# Rotary.net
KiCad netlist of a schematic drawn in Altium Designer
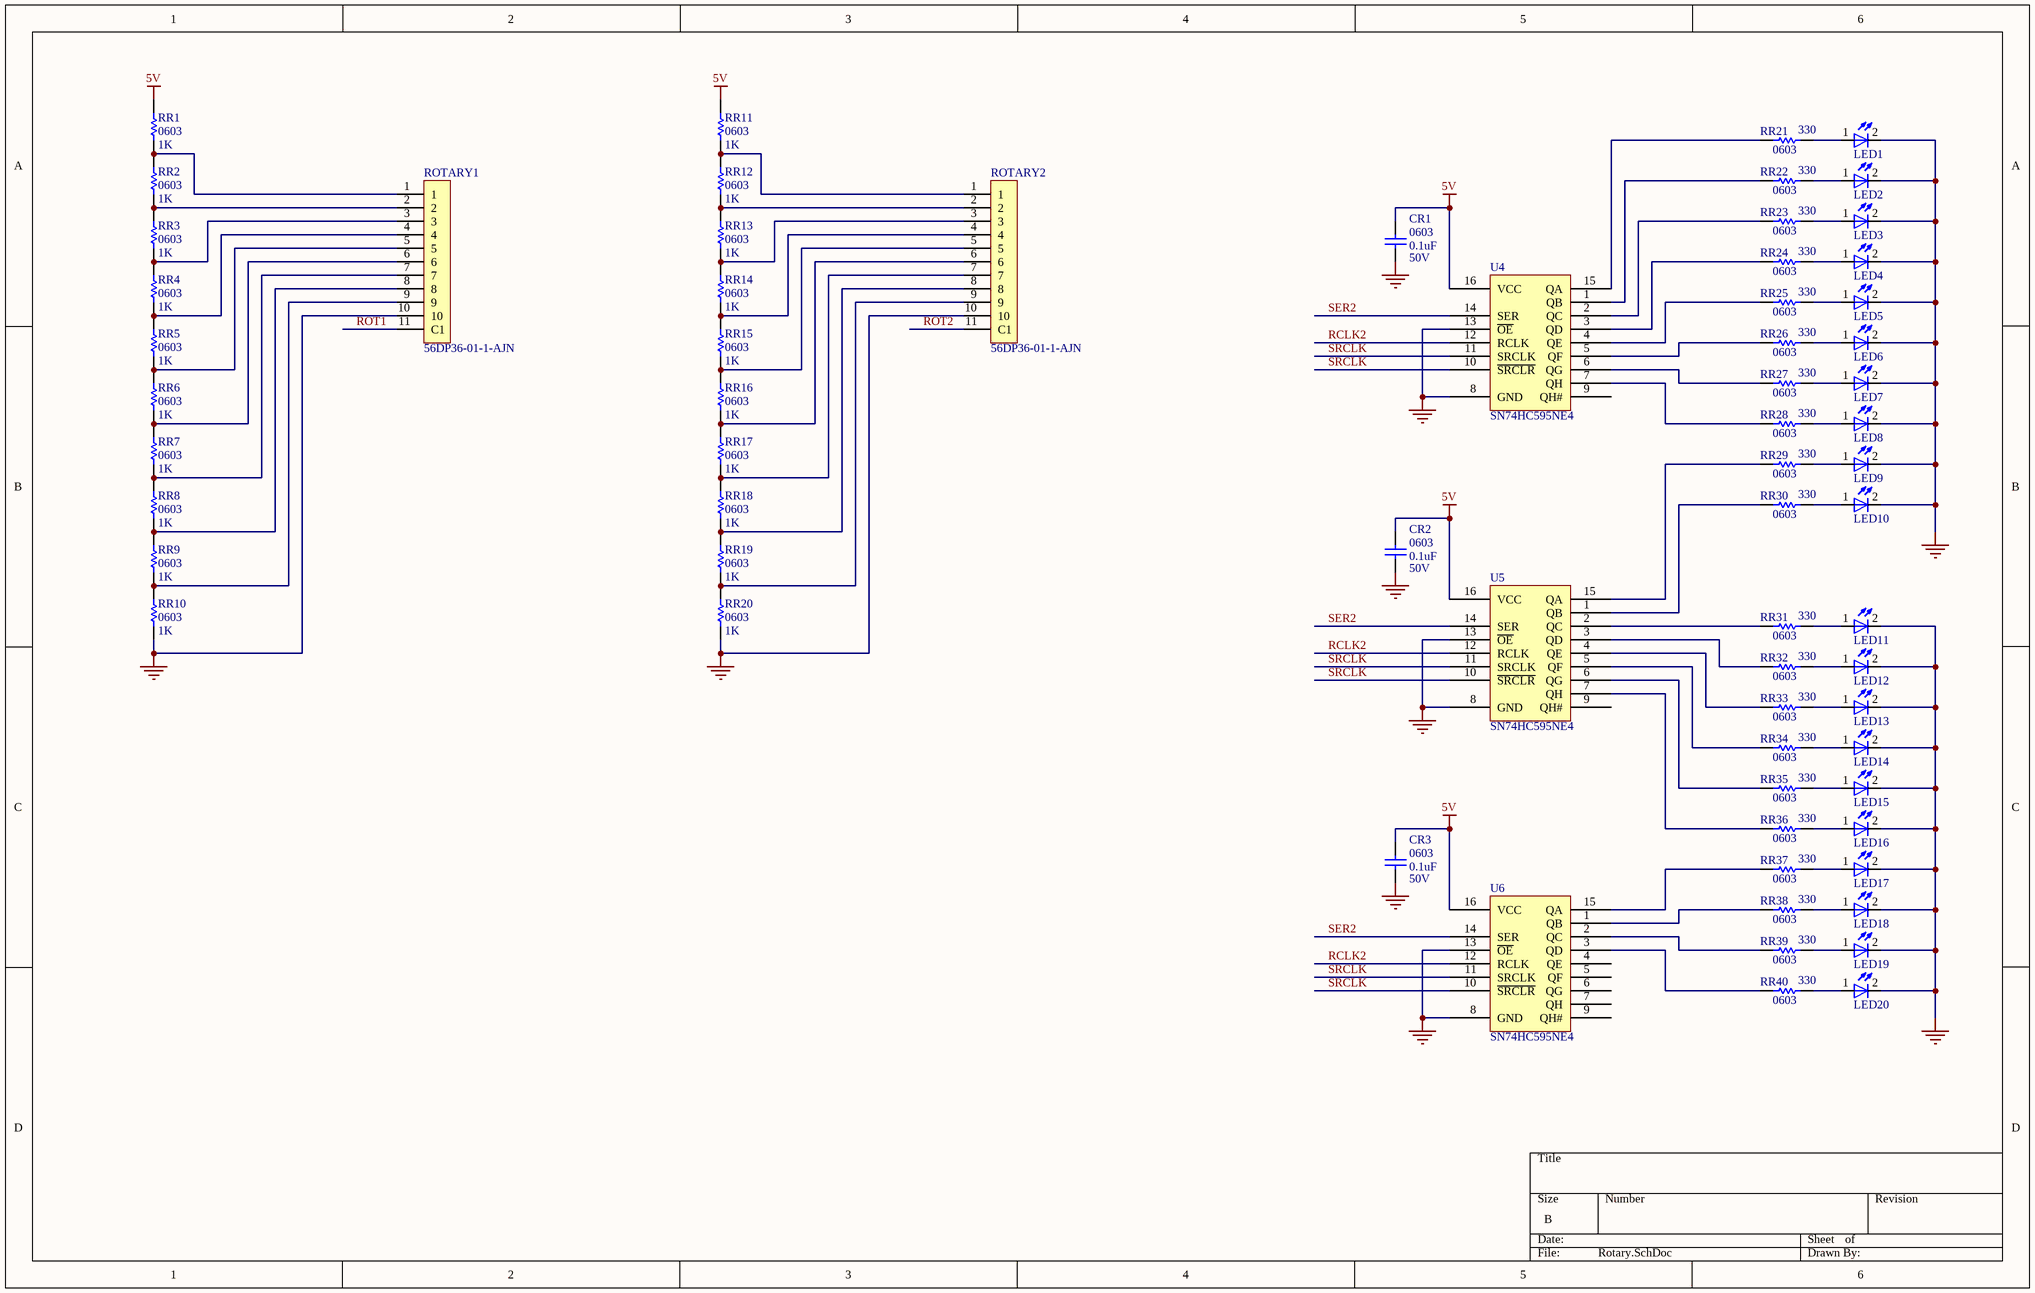
[diagram p0: Rotary.SchDoc]

(export (version "E")
  (design (tool "Eeschema 10.0.6"))
  (components
    (comp (ref "CR1")
      (value "0603")
      (footprint "C0603")
      (description "CAP CER 0.1UF 50V X5R 0603")
      (fields
        (field (name "ALTIUM_VALUE") "0.1uF")
        (field (name "VOLTAGE RATING") "50V")
        (field (name "TOLERANCE") "10%")
      )
      (libsource (lib "Miscellaneous Devices") (part "Cap"))
    )
    (comp (ref "CR2")
      (value "0603")
      (footprint "C0603")
      (description "CAP CER 0.1UF 50V X5R 0603")
      (fields
        (field (name "ALTIUM_VALUE") "0.1uF")
        (field (name "VOLTAGE RATING") "50V")
        (field (name "TOLERANCE") "10%")
      )
      (libsource (lib "Miscellaneous Devices") (part "Cap"))
    )
    (comp (ref "CR3")
      (value "0603")
      (footprint "C0603")
      (description "CAP CER 0.1UF 50V X5R 0603")
      (fields
        (field (name "ALTIUM_VALUE") "0.1uF")
        (field (name "VOLTAGE RATING") "50V")
        (field (name "TOLERANCE") "10%")
      )
      (libsource (lib "Miscellaneous Devices") (part "Cap"))
    )
    (comp (ref "LED1")
      (value "LED 3mm")
      (footprint "LED3mm")
      (description "LED RED DIFFUSED T-1 3/4 T/H")
      (libsource (lib "Schlib") (part "LED 3mm"))
    )
    (comp (ref "LED2")
      (value "LED 3mm")
      (footprint "LED3mm")
      (description "LED RED DIFFUSED T-1 3/4 T/H")
      (libsource (lib "Schlib") (part "LED 3mm"))
    )
    (comp (ref "LED3")
      (value "LED 3mm")
      (footprint "LED3mm")
      (description "LED RED DIFFUSED T-1 3/4 T/H")
      (libsource (lib "Schlib") (part "LED 3mm"))
    )
    (comp (ref "LED4")
      (value "LED 3mm")
      (footprint "LED3mm")
      (description "LED RED DIFFUSED T-1 3/4 T/H")
      (libsource (lib "Schlib") (part "LED 3mm"))
    )
    (comp (ref "LED5")
      (value "LED 3mm")
      (footprint "LED3mm")
      (description "LED RED DIFFUSED T-1 3/4 T/H")
      (libsource (lib "Schlib") (part "LED 3mm"))
    )
    (comp (ref "LED6")
      (value "LED 3mm")
      (footprint "LED3mm")
      (description "LED RED DIFFUSED T-1 3/4 T/H")
      (libsource (lib "Schlib") (part "LED 3mm"))
    )
    (comp (ref "LED7")
      (value "LED 3mm")
      (footprint "LED3mm")
      (description "LED RED DIFFUSED T-1 3/4 T/H")
      (libsource (lib "Schlib") (part "LED 3mm"))
    )
    (comp (ref "LED8")
      (value "LED 3mm")
      (footprint "LED3mm")
      (description "LED RED DIFFUSED T-1 3/4 T/H")
      (libsource (lib "Schlib") (part "LED 3mm"))
    )
    (comp (ref "LED9")
      (value "LED 3mm")
      (footprint "LED3mm")
      (description "LED RED DIFFUSED T-1 3/4 T/H")
      (libsource (lib "Schlib") (part "LED 3mm"))
    )
    (comp (ref "LED10")
      (value "LED 3mm")
      (footprint "LED3mm")
      (description "LED RED DIFFUSED T-1 3/4 T/H")
      (libsource (lib "Schlib") (part "LED 3mm"))
    )
    (comp (ref "LED11")
      (value "LED 3mm")
      (footprint "LED3mm")
      (description "LED RED DIFFUSED T-1 3/4 T/H")
      (libsource (lib "Schlib") (part "LED 3mm"))
    )
    (comp (ref "LED12")
      (value "LED 3mm")
      (footprint "LED3mm")
      (description "LED RED DIFFUSED T-1 3/4 T/H")
      (libsource (lib "Schlib") (part "LED 3mm"))
    )
    (comp (ref "LED13")
      (value "LED 3mm")
      (footprint "LED3mm")
      (description "LED RED DIFFUSED T-1 3/4 T/H")
      (libsource (lib "Schlib") (part "LED 3mm"))
    )
    (comp (ref "LED14")
      (value "LED 3mm")
      (footprint "LED3mm")
      (description "LED RED DIFFUSED T-1 3/4 T/H")
      (libsource (lib "Schlib") (part "LED 3mm"))
    )
    (comp (ref "LED15")
      (value "LED 3mm")
      (footprint "LED3mm")
      (description "LED RED DIFFUSED T-1 3/4 T/H")
      (libsource (lib "Schlib") (part "LED 3mm"))
    )
    (comp (ref "LED16")
      (value "LED 3mm")
      (footprint "LED3mm")
      (description "LED RED DIFFUSED T-1 3/4 T/H")
      (libsource (lib "Schlib") (part "LED 3mm"))
    )
    (comp (ref "LED17")
      (value "LED 3mm")
      (footprint "LED3mm")
      (description "LED RED DIFFUSED T-1 3/4 T/H")
      (libsource (lib "Schlib") (part "LED 3mm"))
    )
    (comp (ref "LED18")
      (value "LED 3mm")
      (footprint "LED3mm")
      (description "LED RED DIFFUSED T-1 3/4 T/H")
      (libsource (lib "Schlib") (part "LED 3mm"))
    )
    (comp (ref "LED19")
      (value "LED 3mm")
      (footprint "LED3mm")
      (description "LED RED DIFFUSED T-1 3/4 T/H")
      (libsource (lib "Schlib") (part "LED 3mm"))
    )
    (comp (ref "LED20")
      (value "LED 3mm")
      (footprint "LED3mm")
      (description "LED RED DIFFUSED T-1 3/4 T/H")
      (libsource (lib "Schlib") (part "LED 3mm"))
    )
    (comp (ref "ROTARY1")
      (value "56DP36-01-1-AJN")
      (footprint "56DP36-01-1-AJN")
      (description "Switch Rotary SP Flatted Shaft PC Pins 0.2A 115VAC 30VDC")
      (libsource (lib "Schlib") (part "56DP36-01-1-AJN"))
    )
    (comp (ref "ROTARY2")
      (value "56DP36-01-1-AJN")
      (footprint "56DP36-01-1-AJN")
      (description "Switch Rotary SP Flatted Shaft PC Pins 0.2A 115VAC 30VDC")
      (libsource (lib "Schlib") (part "56DP36-01-1-AJN"))
    )
    (comp (ref "RR1")
      (value "0603")
      (footprint "R0603")
      (description "RES SMD 1K OHM 1% 1/10W 0603")
      (fields
        (field (name "ALTIUM_VALUE") "1K")
        (field (name "MANUFACTURER") "Yageo")
        (field (name "MANUFACTURER PART NUMBER") "RC0603FR-071KL")
      )
      (libsource (lib "Miscellaneous Devices") (part "Res1"))
    )
    (comp (ref "RR2")
      (value "0603")
      (footprint "R0603")
      (description "RES SMD 1K OHM 1% 1/10W 0603")
      (fields
        (field (name "ALTIUM_VALUE") "1K")
        (field (name "MANUFACTURER") "Yageo")
        (field (name "MANUFACTURER PART NUMBER") "RC0603FR-071KL")
      )
      (libsource (lib "Miscellaneous Devices") (part "Res1"))
    )
    (comp (ref "RR3")
      (value "0603")
      (footprint "R0603")
      (description "RES SMD 1K OHM 1% 1/10W 0603")
      (fields
        (field (name "ALTIUM_VALUE") "1K")
        (field (name "MANUFACTURER") "Yageo")
        (field (name "MANUFACTURER PART NUMBER") "RC0603FR-071KL")
      )
      (libsource (lib "Miscellaneous Devices") (part "Res1"))
    )
    (comp (ref "RR4")
      (value "0603")
      (footprint "R0603")
      (description "RES SMD 1K OHM 1% 1/10W 0603")
      (fields
        (field (name "ALTIUM_VALUE") "1K")
        (field (name "MANUFACTURER") "Yageo")
        (field (name "MANUFACTURER PART NUMBER") "RC0603FR-071KL")
      )
      (libsource (lib "Miscellaneous Devices") (part "Res1"))
    )
    (comp (ref "RR5")
      (value "0603")
      (footprint "R0603")
      (description "RES SMD 1K OHM 1% 1/10W 0603")
      (fields
        (field (name "ALTIUM_VALUE") "1K")
        (field (name "MANUFACTURER") "Yageo")
        (field (name "MANUFACTURER PART NUMBER") "RC0603FR-071KL")
      )
      (libsource (lib "Miscellaneous Devices") (part "Res1"))
    )
    (comp (ref "RR6")
      (value "0603")
      (footprint "R0603")
      (description "RES SMD 1K OHM 1% 1/10W 0603")
      (fields
        (field (name "ALTIUM_VALUE") "1K")
        (field (name "MANUFACTURER") "Yageo")
        (field (name "MANUFACTURER PART NUMBER") "RC0603FR-071KL")
      )
      (libsource (lib "Miscellaneous Devices") (part "Res1"))
    )
    (comp (ref "RR7")
      (value "0603")
      (footprint "R0603")
      (description "RES SMD 1K OHM 1% 1/10W 0603")
      (fields
        (field (name "ALTIUM_VALUE") "1K")
        (field (name "MANUFACTURER") "Yageo")
        (field (name "MANUFACTURER PART NUMBER") "RC0603FR-071KL")
      )
      (libsource (lib "Miscellaneous Devices") (part "Res1"))
    )
    (comp (ref "RR8")
      (value "0603")
      (footprint "R0603")
      (description "RES SMD 1K OHM 1% 1/10W 0603")
      (fields
        (field (name "ALTIUM_VALUE") "1K")
        (field (name "MANUFACTURER") "Yageo")
        (field (name "MANUFACTURER PART NUMBER") "RC0603FR-071KL")
      )
      (libsource (lib "Miscellaneous Devices") (part "Res1"))
    )
    (comp (ref "RR9")
      (value "0603")
      (footprint "R0603")
      (description "RES SMD 1K OHM 1% 1/10W 0603")
      (fields
        (field (name "ALTIUM_VALUE") "1K")
        (field (name "MANUFACTURER") "Yageo")
        (field (name "MANUFACTURER PART NUMBER") "RC0603FR-071KL")
      )
      (libsource (lib "Miscellaneous Devices") (part "Res1"))
    )
    (comp (ref "RR10")
      (value "0603")
      (footprint "R0603")
      (description "RES SMD 1K OHM 1% 1/10W 0603")
      (fields
        (field (name "ALTIUM_VALUE") "1K")
        (field (name "MANUFACTURER") "Yageo")
        (field (name "MANUFACTURER PART NUMBER") "RC0603FR-071KL")
      )
      (libsource (lib "Miscellaneous Devices") (part "Res1"))
    )
    (comp (ref "RR11")
      (value "0603")
      (footprint "R0603")
      (description "RES SMD 1K OHM 1% 1/10W 0603")
      (fields
        (field (name "ALTIUM_VALUE") "1K")
        (field (name "MANUFACTURER") "Yageo")
        (field (name "MANUFACTURER PART NUMBER") "RC0603FR-071KL")
      )
      (libsource (lib "Miscellaneous Devices") (part "Res1"))
    )
    (comp (ref "RR12")
      (value "0603")
      (footprint "R0603")
      (description "RES SMD 1K OHM 1% 1/10W 0603")
      (fields
        (field (name "ALTIUM_VALUE") "1K")
        (field (name "MANUFACTURER") "Yageo")
        (field (name "MANUFACTURER PART NUMBER") "RC0603FR-071KL")
      )
      (libsource (lib "Miscellaneous Devices") (part "Res1"))
    )
    (comp (ref "RR13")
      (value "0603")
      (footprint "R0603")
      (description "RES SMD 1K OHM 1% 1/10W 0603")
      (fields
        (field (name "ALTIUM_VALUE") "1K")
        (field (name "MANUFACTURER") "Yageo")
        (field (name "MANUFACTURER PART NUMBER") "RC0603FR-071KL")
      )
      (libsource (lib "Miscellaneous Devices") (part "Res1"))
    )
    (comp (ref "RR14")
      (value "0603")
      (footprint "R0603")
      (description "RES SMD 1K OHM 1% 1/10W 0603")
      (fields
        (field (name "ALTIUM_VALUE") "1K")
        (field (name "MANUFACTURER") "Yageo")
        (field (name "MANUFACTURER PART NUMBER") "RC0603FR-071KL")
      )
      (libsource (lib "Miscellaneous Devices") (part "Res1"))
    )
    (comp (ref "RR15")
      (value "0603")
      (footprint "R0603")
      (description "RES SMD 1K OHM 1% 1/10W 0603")
      (fields
        (field (name "ALTIUM_VALUE") "1K")
        (field (name "MANUFACTURER") "Yageo")
        (field (name "MANUFACTURER PART NUMBER") "RC0603FR-071KL")
      )
      (libsource (lib "Miscellaneous Devices") (part "Res1"))
    )
    (comp (ref "RR16")
      (value "0603")
      (footprint "R0603")
      (description "RES SMD 1K OHM 1% 1/10W 0603")
      (fields
        (field (name "ALTIUM_VALUE") "1K")
        (field (name "MANUFACTURER") "Yageo")
        (field (name "MANUFACTURER PART NUMBER") "RC0603FR-071KL")
      )
      (libsource (lib "Miscellaneous Devices") (part "Res1"))
    )
    (comp (ref "RR17")
      (value "0603")
      (footprint "R0603")
      (description "RES SMD 1K OHM 1% 1/10W 0603")
      (fields
        (field (name "ALTIUM_VALUE") "1K")
        (field (name "MANUFACTURER") "Yageo")
        (field (name "MANUFACTURER PART NUMBER") "RC0603FR-071KL")
      )
      (libsource (lib "Miscellaneous Devices") (part "Res1"))
    )
    (comp (ref "RR18")
      (value "0603")
      (footprint "R0603")
      (description "RES SMD 1K OHM 1% 1/10W 0603")
      (fields
        (field (name "ALTIUM_VALUE") "1K")
        (field (name "MANUFACTURER") "Yageo")
        (field (name "MANUFACTURER PART NUMBER") "RC0603FR-071KL")
      )
      (libsource (lib "Miscellaneous Devices") (part "Res1"))
    )
    (comp (ref "RR19")
      (value "0603")
      (footprint "R0603")
      (description "RES SMD 1K OHM 1% 1/10W 0603")
      (fields
        (field (name "ALTIUM_VALUE") "1K")
        (field (name "MANUFACTURER") "Yageo")
        (field (name "MANUFACTURER PART NUMBER") "RC0603FR-071KL")
      )
      (libsource (lib "Miscellaneous Devices") (part "Res1"))
    )
    (comp (ref "RR20")
      (value "0603")
      (footprint "R0603")
      (description "RES SMD 1K OHM 1% 1/10W 0603")
      (fields
        (field (name "ALTIUM_VALUE") "1K")
        (field (name "MANUFACTURER") "Yageo")
        (field (name "MANUFACTURER PART NUMBER") "RC0603FR-071KL")
      )
      (libsource (lib "Miscellaneous Devices") (part "Res1"))
    )
    (comp (ref "RR21")
      (value "0603")
      (footprint "R0603")
      (description "RES SMD 330 OHM 1% 1/10W 0603")
      (fields (field (name "ALTIUM_VALUE") "330") (field (name "TOLERANCE") "1%"))
      (libsource (lib "Miscellaneous Devices") (part "Res1"))
    )
    (comp (ref "RR22")
      (value "0603")
      (footprint "R0603")
      (description "RES SMD 330 OHM 1% 1/10W 0603")
      (fields (field (name "ALTIUM_VALUE") "330") (field (name "TOLERANCE") "1%"))
      (libsource (lib "Miscellaneous Devices") (part "Res1"))
    )
    (comp (ref "RR23")
      (value "0603")
      (footprint "R0603")
      (description "RES SMD 330 OHM 1% 1/10W 0603")
      (fields (field (name "ALTIUM_VALUE") "330") (field (name "TOLERANCE") "1%"))
      (libsource (lib "Miscellaneous Devices") (part "Res1"))
    )
    (comp (ref "RR24")
      (value "0603")
      (footprint "R0603")
      (description "RES SMD 330 OHM 1% 1/10W 0603")
      (fields (field (name "ALTIUM_VALUE") "330") (field (name "TOLERANCE") "1%"))
      (libsource (lib "Miscellaneous Devices") (part "Res1"))
    )
    (comp (ref "RR25")
      (value "0603")
      (footprint "R0603")
      (description "RES SMD 330 OHM 1% 1/10W 0603")
      (fields (field (name "ALTIUM_VALUE") "330") (field (name "TOLERANCE") "1%"))
      (libsource (lib "Miscellaneous Devices") (part "Res1"))
    )
    (comp (ref "RR26")
      (value "0603")
      (footprint "R0603")
      (description "RES SMD 330 OHM 1% 1/10W 0603")
      (fields (field (name "ALTIUM_VALUE") "330") (field (name "TOLERANCE") "1%"))
      (libsource (lib "Miscellaneous Devices") (part "Res1"))
    )
    (comp (ref "RR27")
      (value "0603")
      (footprint "R0603")
      (description "RES SMD 330 OHM 1% 1/10W 0603")
      (fields (field (name "ALTIUM_VALUE") "330") (field (name "TOLERANCE") "1%"))
      (libsource (lib "Miscellaneous Devices") (part "Res1"))
    )
    (comp (ref "RR28")
      (value "0603")
      (footprint "R0603")
      (description "RES SMD 330 OHM 1% 1/10W 0603")
      (fields (field (name "ALTIUM_VALUE") "330") (field (name "TOLERANCE") "1%"))
      (libsource (lib "Miscellaneous Devices") (part "Res1"))
    )
    (comp (ref "RR29")
      (value "0603")
      (footprint "R0603")
      (description "RES SMD 330 OHM 1% 1/10W 0603")
      (fields (field (name "ALTIUM_VALUE") "330") (field (name "TOLERANCE") "1%"))
      (libsource (lib "Miscellaneous Devices") (part "Res1"))
    )
    (comp (ref "RR30")
      (value "0603")
      (footprint "R0603")
      (description "RES SMD 330 OHM 1% 1/10W 0603")
      (fields (field (name "ALTIUM_VALUE") "330") (field (name "TOLERANCE") "1%"))
      (libsource (lib "Miscellaneous Devices") (part "Res1"))
    )
    (comp (ref "RR31")
      (value "0603")
      (footprint "R0603")
      (description "RES SMD 330 OHM 1% 1/10W 0603")
      (fields (field (name "ALTIUM_VALUE") "330") (field (name "TOLERANCE") "1%"))
      (libsource (lib "Miscellaneous Devices") (part "Res1"))
    )
    (comp (ref "RR32")
      (value "0603")
      (footprint "R0603")
      (description "RES SMD 330 OHM 1% 1/10W 0603")
      (fields (field (name "ALTIUM_VALUE") "330") (field (name "TOLERANCE") "1%"))
      (libsource (lib "Miscellaneous Devices") (part "Res1"))
    )
    (comp (ref "RR33")
      (value "0603")
      (footprint "R0603")
      (description "RES SMD 330 OHM 1% 1/10W 0603")
      (fields (field (name "ALTIUM_VALUE") "330") (field (name "TOLERANCE") "1%"))
      (libsource (lib "Miscellaneous Devices") (part "Res1"))
    )
    (comp (ref "RR34")
      (value "0603")
      (footprint "R0603")
      (description "RES SMD 330 OHM 1% 1/10W 0603")
      (fields (field (name "ALTIUM_VALUE") "330") (field (name "TOLERANCE") "1%"))
      (libsource (lib "Miscellaneous Devices") (part "Res1"))
    )
    (comp (ref "RR35")
      (value "0603")
      (footprint "R0603")
      (description "RES SMD 330 OHM 1% 1/10W 0603")
      (fields (field (name "ALTIUM_VALUE") "330") (field (name "TOLERANCE") "1%"))
      (libsource (lib "Miscellaneous Devices") (part "Res1"))
    )
    (comp (ref "RR36")
      (value "0603")
      (footprint "R0603")
      (description "RES SMD 330 OHM 1% 1/10W 0603")
      (fields (field (name "ALTIUM_VALUE") "330") (field (name "TOLERANCE") "1%"))
      (libsource (lib "Miscellaneous Devices") (part "Res1"))
    )
    (comp (ref "RR37")
      (value "0603")
      (footprint "R0603")
      (description "RES SMD 330 OHM 1% 1/10W 0603")
      (fields (field (name "ALTIUM_VALUE") "330") (field (name "TOLERANCE") "1%"))
      (libsource (lib "Miscellaneous Devices") (part "Res1"))
    )
    (comp (ref "RR38")
      (value "0603")
      (footprint "R0603")
      (description "RES SMD 330 OHM 1% 1/10W 0603")
      (fields (field (name "ALTIUM_VALUE") "330") (field (name "TOLERANCE") "1%"))
      (libsource (lib "Miscellaneous Devices") (part "Res1"))
    )
    (comp (ref "RR39")
      (value "0603")
      (footprint "R0603")
      (description "RES SMD 330 OHM 1% 1/10W 0603")
      (fields (field (name "ALTIUM_VALUE") "330") (field (name "TOLERANCE") "1%"))
      (libsource (lib "Miscellaneous Devices") (part "Res1"))
    )
    (comp (ref "RR40")
      (value "0603")
      (footprint "R0603")
      (description "RES SMD 330 OHM 1% 1/10W 0603")
      (fields (field (name "ALTIUM_VALUE") "330") (field (name "TOLERANCE") "1%"))
      (libsource (lib "Miscellaneous Devices") (part "Res1"))
    )
    (comp (ref "U4")
      (value "SN74HC595NE4")
      (footprint "DIP794W53P254L1930H508Q16N")
      (description "Counter Shift Registers 8-Bit Shift Register")
      (libsource (lib "Schlib") (part "SN74HC595NE4"))
    )
    (comp (ref "U5")
      (value "SN74HC595NE4")
      (footprint "DIP794W53P254L1930H508Q16N")
      (description "Counter Shift Registers 8-Bit Shift Register")
      (libsource (lib "Schlib") (part "SN74HC595NE4"))
    )
    (comp (ref "U6")
      (value "SN74HC595NE4")
      (footprint "DIP794W53P254L1930H508Q16N")
      (description "Counter Shift Registers 8-Bit Shift Register")
      (libsource (lib "Schlib") (part "SN74HC595NE4"))
    )
  )
  (nets
    (net (code "1") (name "/RCLK2") (class "Default")
      (node (ref "U4") (pin "12") (pinfunction "RCLK_12") (pintype "passive"))
      (node (ref "U5") (pin "12") (pinfunction "RCLK_12") (pintype "passive"))
      (node (ref "U6") (pin "12") (pinfunction "RCLK_12") (pintype "passive"))
    )
    (net (code "2") (name "/ROT1") (class "Default")
      (node (ref "ROTARY1") (pin "11") (pinfunction "C1_11") (pintype "passive"))
    )
    (net (code "3") (name "/ROT2") (class "Default")
      (node (ref "ROTARY2") (pin "11") (pinfunction "C1_11") (pintype "passive"))
    )
    (net (code "4") (name "/SER2") (class "Default")
      (node (ref "U4") (pin "14") (pinfunction "SER_14") (pintype "passive"))
      (node (ref "U5") (pin "14") (pinfunction "SER_14") (pintype "passive"))
      (node (ref "U6") (pin "14") (pinfunction "SER_14") (pintype "passive"))
    )
    (net (code "5") (name "/SRCLK") (class "Default")
      (node (ref "U4") (pin "11") (pinfunction "SRCLK_11") (pintype "passive"))
      (node (ref "U5") (pin "11") (pinfunction "SRCLK_11") (pintype "passive"))
      (node (ref "U6") (pin "11") (pinfunction "SRCLK_11") (pintype "passive"))
    )
    (net (code "6") (name "/~{SRCLK}") (class "Default")
      (node (ref "U4") (pin "10") (pinfunction "~{SRCLR}_10") (pintype "passive"))
      (node (ref "U5") (pin "10") (pinfunction "~{SRCLR}_10") (pintype "passive"))
      (node (ref "U6") (pin "10") (pinfunction "~{SRCLR}_10") (pintype "passive"))
    )
    (net (code "7") (name "5V") (class "Default")
      (node (ref "CR1") (pin "2") (pinfunction "2_2") (pintype "passive"))
      (node (ref "CR2") (pin "2") (pinfunction "2_2") (pintype "passive"))
      (node (ref "CR3") (pin "2") (pinfunction "2_2") (pintype "passive"))
      (node (ref "RR1") (pin "1") (pinfunction "1_1") (pintype "passive"))
      (node (ref "RR11") (pin "1") (pinfunction "1_1") (pintype "passive"))
      (node (ref "U4") (pin "16") (pinfunction "VCC_16") (pintype "passive"))
      (node (ref "U5") (pin "16") (pinfunction "VCC_16") (pintype "passive"))
      (node (ref "U6") (pin "16") (pinfunction "VCC_16") (pintype "passive"))
    )
    (net (code "8") (name "GND") (class "Default")
      (node (ref "CR1") (pin "1") (pinfunction "1_1") (pintype "passive"))
      (node (ref "CR2") (pin "1") (pinfunction "1_1") (pintype "passive"))
      (node (ref "CR3") (pin "1") (pinfunction "1_1") (pintype "passive"))
      (node (ref "LED1") (pin "2") (pinfunction "2_2") (pintype "passive"))
      (node (ref "LED10") (pin "2") (pinfunction "2_2") (pintype "passive"))
      (node (ref "LED11") (pin "2") (pinfunction "2_2") (pintype "passive"))
      (node (ref "LED12") (pin "2") (pinfunction "2_2") (pintype "passive"))
      (node (ref "LED13") (pin "2") (pinfunction "2_2") (pintype "passive"))
      (node (ref "LED14") (pin "2") (pinfunction "2_2") (pintype "passive"))
      (node (ref "LED15") (pin "2") (pinfunction "2_2") (pintype "passive"))
      (node (ref "LED16") (pin "2") (pinfunction "2_2") (pintype "passive"))
      (node (ref "LED17") (pin "2") (pinfunction "2_2") (pintype "passive"))
      (node (ref "LED18") (pin "2") (pinfunction "2_2") (pintype "passive"))
      (node (ref "LED19") (pin "2") (pinfunction "2_2") (pintype "passive"))
      (node (ref "LED2") (pin "2") (pinfunction "2_2") (pintype "passive"))
      (node (ref "LED20") (pin "2") (pinfunction "2_2") (pintype "passive"))
      (node (ref "LED3") (pin "2") (pinfunction "2_2") (pintype "passive"))
      (node (ref "LED4") (pin "2") (pinfunction "2_2") (pintype "passive"))
      (node (ref "LED5") (pin "2") (pinfunction "2_2") (pintype "passive"))
      (node (ref "LED6") (pin "2") (pinfunction "2_2") (pintype "passive"))
      (node (ref "LED7") (pin "2") (pinfunction "2_2") (pintype "passive"))
      (node (ref "LED8") (pin "2") (pinfunction "2_2") (pintype "passive"))
      (node (ref "LED9") (pin "2") (pinfunction "2_2") (pintype "passive"))
      (node (ref "ROTARY1") (pin "10") (pinfunction "10_10") (pintype "passive"))
      (node (ref "ROTARY2") (pin "10") (pinfunction "10_10") (pintype "passive"))
      (node (ref "RR10") (pin "2") (pinfunction "2_2") (pintype "passive"))
      (node (ref "RR20") (pin "2") (pinfunction "2_2") (pintype "passive"))
      (node (ref "U4") (pin "13") (pinfunction "~{OE}_13") (pintype "passive"))
      (node (ref "U4") (pin "8") (pinfunction "GND_8") (pintype "passive"))
      (node (ref "U5") (pin "13") (pinfunction "~{OE}_13") (pintype "passive"))
      (node (ref "U5") (pin "8") (pinfunction "GND_8") (pintype "passive"))
      (node (ref "U6") (pin "13") (pinfunction "~{OE}_13") (pintype "passive"))
      (node (ref "U6") (pin "8") (pinfunction "GND_8") (pintype "passive"))
    )
    (net (code "9") (name "Net-(LED1-Pad1)") (class "Default")
      (node (ref "LED1") (pin "1") (pinfunction "1_1") (pintype "passive"))
      (node (ref "RR21") (pin "2") (pinfunction "2_2") (pintype "passive"))
    )
    (net (code "10") (name "Net-(LED2-Pad1)") (class "Default")
      (node (ref "LED2") (pin "1") (pinfunction "1_1") (pintype "passive"))
      (node (ref "RR22") (pin "2") (pinfunction "2_2") (pintype "passive"))
    )
    (net (code "11") (name "Net-(LED3-Pad1)") (class "Default")
      (node (ref "LED3") (pin "1") (pinfunction "1_1") (pintype "passive"))
      (node (ref "RR23") (pin "2") (pinfunction "2_2") (pintype "passive"))
    )
    (net (code "12") (name "Net-(LED4-Pad1)") (class "Default")
      (node (ref "LED4") (pin "1") (pinfunction "1_1") (pintype "passive"))
      (node (ref "RR24") (pin "2") (pinfunction "2_2") (pintype "passive"))
    )
    (net (code "13") (name "Net-(LED5-Pad1)") (class "Default")
      (node (ref "LED5") (pin "1") (pinfunction "1_1") (pintype "passive"))
      (node (ref "RR25") (pin "2") (pinfunction "2_2") (pintype "passive"))
    )
    (net (code "14") (name "Net-(LED6-Pad1)") (class "Default")
      (node (ref "LED6") (pin "1") (pinfunction "1_1") (pintype "passive"))
      (node (ref "RR26") (pin "2") (pinfunction "2_2") (pintype "passive"))
    )
    (net (code "15") (name "Net-(LED7-Pad1)") (class "Default")
      (node (ref "LED7") (pin "1") (pinfunction "1_1") (pintype "passive"))
      (node (ref "RR27") (pin "2") (pinfunction "2_2") (pintype "passive"))
    )
    (net (code "16") (name "Net-(LED8-Pad1)") (class "Default")
      (node (ref "LED8") (pin "1") (pinfunction "1_1") (pintype "passive"))
      (node (ref "RR28") (pin "2") (pinfunction "2_2") (pintype "passive"))
    )
    (net (code "17") (name "Net-(LED9-Pad1)") (class "Default")
      (node (ref "LED9") (pin "1") (pinfunction "1_1") (pintype "passive"))
      (node (ref "RR29") (pin "2") (pinfunction "2_2") (pintype "passive"))
    )
    (net (code "18") (name "Net-(LED10-Pad1)") (class "Default")
      (node (ref "LED10") (pin "1") (pinfunction "1_1") (pintype "passive"))
      (node (ref "RR30") (pin "2") (pinfunction "2_2") (pintype "passive"))
    )
    (net (code "19") (name "Net-(LED11-Pad1)") (class "Default")
      (node (ref "LED11") (pin "1") (pinfunction "1_1") (pintype "passive"))
      (node (ref "RR31") (pin "2") (pinfunction "2_2") (pintype "passive"))
    )
    (net (code "20") (name "Net-(LED12-Pad1)") (class "Default")
      (node (ref "LED12") (pin "1") (pinfunction "1_1") (pintype "passive"))
      (node (ref "RR32") (pin "2") (pinfunction "2_2") (pintype "passive"))
    )
    (net (code "21") (name "Net-(LED13-Pad1)") (class "Default")
      (node (ref "LED13") (pin "1") (pinfunction "1_1") (pintype "passive"))
      (node (ref "RR33") (pin "2") (pinfunction "2_2") (pintype "passive"))
    )
    (net (code "22") (name "Net-(LED14-Pad1)") (class "Default")
      (node (ref "LED14") (pin "1") (pinfunction "1_1") (pintype "passive"))
      (node (ref "RR34") (pin "2") (pinfunction "2_2") (pintype "passive"))
    )
    (net (code "23") (name "Net-(LED15-Pad1)") (class "Default")
      (node (ref "LED15") (pin "1") (pinfunction "1_1") (pintype "passive"))
      (node (ref "RR35") (pin "2") (pinfunction "2_2") (pintype "passive"))
    )
    (net (code "24") (name "Net-(LED16-Pad1)") (class "Default")
      (node (ref "LED16") (pin "1") (pinfunction "1_1") (pintype "passive"))
      (node (ref "RR36") (pin "2") (pinfunction "2_2") (pintype "passive"))
    )
    (net (code "25") (name "Net-(LED17-Pad1)") (class "Default")
      (node (ref "LED17") (pin "1") (pinfunction "1_1") (pintype "passive"))
      (node (ref "RR37") (pin "2") (pinfunction "2_2") (pintype "passive"))
    )
    (net (code "26") (name "Net-(LED18-Pad1)") (class "Default")
      (node (ref "LED18") (pin "1") (pinfunction "1_1") (pintype "passive"))
      (node (ref "RR38") (pin "2") (pinfunction "2_2") (pintype "passive"))
    )
    (net (code "27") (name "Net-(LED19-Pad1)") (class "Default")
      (node (ref "LED19") (pin "1") (pinfunction "1_1") (pintype "passive"))
      (node (ref "RR39") (pin "2") (pinfunction "2_2") (pintype "passive"))
    )
    (net (code "28") (name "Net-(LED20-Pad1)") (class "Default")
      (node (ref "LED20") (pin "1") (pinfunction "1_1") (pintype "passive"))
      (node (ref "RR40") (pin "2") (pinfunction "2_2") (pintype "passive"))
    )
    (net (code "29") (name "Net-(ROTARY1-Pad1)") (class "Default")
      (node (ref "ROTARY1") (pin "1") (pinfunction "1_1") (pintype "passive"))
      (node (ref "RR1") (pin "2") (pinfunction "2_2") (pintype "passive"))
      (node (ref "RR2") (pin "1") (pinfunction "1_1") (pintype "passive"))
    )
    (net (code "30") (name "Net-(ROTARY1-Pad2)") (class "Default")
      (node (ref "ROTARY1") (pin "2") (pinfunction "2_2") (pintype "passive"))
      (node (ref "RR2") (pin "2") (pinfunction "2_2") (pintype "passive"))
      (node (ref "RR3") (pin "1") (pinfunction "1_1") (pintype "passive"))
    )
    (net (code "31") (name "Net-(ROTARY1-Pad3)") (class "Default")
      (node (ref "ROTARY1") (pin "3") (pinfunction "3_3") (pintype "passive"))
      (node (ref "RR3") (pin "2") (pinfunction "2_2") (pintype "passive"))
      (node (ref "RR4") (pin "1") (pinfunction "1_1") (pintype "passive"))
    )
    (net (code "32") (name "Net-(ROTARY1-Pad4)") (class "Default")
      (node (ref "ROTARY1") (pin "4") (pinfunction "4_4") (pintype "passive"))
      (node (ref "RR4") (pin "2") (pinfunction "2_2") (pintype "passive"))
      (node (ref "RR5") (pin "1") (pinfunction "1_1") (pintype "passive"))
    )
    (net (code "33") (name "Net-(ROTARY1-Pad5)") (class "Default")
      (node (ref "ROTARY1") (pin "5") (pinfunction "5_5") (pintype "passive"))
      (node (ref "RR5") (pin "2") (pinfunction "2_2") (pintype "passive"))
      (node (ref "RR6") (pin "1") (pinfunction "1_1") (pintype "passive"))
    )
    (net (code "34") (name "Net-(ROTARY1-Pad6)") (class "Default")
      (node (ref "ROTARY1") (pin "6") (pinfunction "6_6") (pintype "passive"))
      (node (ref "RR6") (pin "2") (pinfunction "2_2") (pintype "passive"))
      (node (ref "RR7") (pin "1") (pinfunction "1_1") (pintype "passive"))
    )
    (net (code "35") (name "Net-(ROTARY1-Pad7)") (class "Default")
      (node (ref "ROTARY1") (pin "7") (pinfunction "7_7") (pintype "passive"))
      (node (ref "RR7") (pin "2") (pinfunction "2_2") (pintype "passive"))
      (node (ref "RR8") (pin "1") (pinfunction "1_1") (pintype "passive"))
    )
    (net (code "36") (name "Net-(ROTARY1-Pad8)") (class "Default")
      (node (ref "ROTARY1") (pin "8") (pinfunction "8_8") (pintype "passive"))
      (node (ref "RR8") (pin "2") (pinfunction "2_2") (pintype "passive"))
      (node (ref "RR9") (pin "1") (pinfunction "1_1") (pintype "passive"))
    )
    (net (code "37") (name "Net-(ROTARY1-Pad9)") (class "Default")
      (node (ref "ROTARY1") (pin "9") (pinfunction "9_9") (pintype "passive"))
      (node (ref "RR10") (pin "1") (pinfunction "1_1") (pintype "passive"))
      (node (ref "RR9") (pin "2") (pinfunction "2_2") (pintype "passive"))
    )
    (net (code "38") (name "Net-(ROTARY2-Pad1)") (class "Default")
      (node (ref "ROTARY2") (pin "1") (pinfunction "1_1") (pintype "passive"))
      (node (ref "RR11") (pin "2") (pinfunction "2_2") (pintype "passive"))
      (node (ref "RR12") (pin "1") (pinfunction "1_1") (pintype "passive"))
    )
    (net (code "39") (name "Net-(ROTARY2-Pad2)") (class "Default")
      (node (ref "ROTARY2") (pin "2") (pinfunction "2_2") (pintype "passive"))
      (node (ref "RR12") (pin "2") (pinfunction "2_2") (pintype "passive"))
      (node (ref "RR13") (pin "1") (pinfunction "1_1") (pintype "passive"))
    )
    (net (code "40") (name "Net-(ROTARY2-Pad3)") (class "Default")
      (node (ref "ROTARY2") (pin "3") (pinfunction "3_3") (pintype "passive"))
      (node (ref "RR13") (pin "2") (pinfunction "2_2") (pintype "passive"))
      (node (ref "RR14") (pin "1") (pinfunction "1_1") (pintype "passive"))
    )
    (net (code "41") (name "Net-(ROTARY2-Pad4)") (class "Default")
      (node (ref "ROTARY2") (pin "4") (pinfunction "4_4") (pintype "passive"))
      (node (ref "RR14") (pin "2") (pinfunction "2_2") (pintype "passive"))
      (node (ref "RR15") (pin "1") (pinfunction "1_1") (pintype "passive"))
    )
    (net (code "42") (name "Net-(ROTARY2-Pad5)") (class "Default")
      (node (ref "ROTARY2") (pin "5") (pinfunction "5_5") (pintype "passive"))
      (node (ref "RR15") (pin "2") (pinfunction "2_2") (pintype "passive"))
      (node (ref "RR16") (pin "1") (pinfunction "1_1") (pintype "passive"))
    )
    (net (code "43") (name "Net-(ROTARY2-Pad6)") (class "Default")
      (node (ref "ROTARY2") (pin "6") (pinfunction "6_6") (pintype "passive"))
      (node (ref "RR16") (pin "2") (pinfunction "2_2") (pintype "passive"))
      (node (ref "RR17") (pin "1") (pinfunction "1_1") (pintype "passive"))
    )
    (net (code "44") (name "Net-(ROTARY2-Pad7)") (class "Default")
      (node (ref "ROTARY2") (pin "7") (pinfunction "7_7") (pintype "passive"))
      (node (ref "RR17") (pin "2") (pinfunction "2_2") (pintype "passive"))
      (node (ref "RR18") (pin "1") (pinfunction "1_1") (pintype "passive"))
    )
    (net (code "45") (name "Net-(ROTARY2-Pad8)") (class "Default")
      (node (ref "ROTARY2") (pin "8") (pinfunction "8_8") (pintype "passive"))
      (node (ref "RR18") (pin "2") (pinfunction "2_2") (pintype "passive"))
      (node (ref "RR19") (pin "1") (pinfunction "1_1") (pintype "passive"))
    )
    (net (code "46") (name "Net-(ROTARY2-Pad9)") (class "Default")
      (node (ref "ROTARY2") (pin "9") (pinfunction "9_9") (pintype "passive"))
      (node (ref "RR19") (pin "2") (pinfunction "2_2") (pintype "passive"))
      (node (ref "RR20") (pin "1") (pinfunction "1_1") (pintype "passive"))
    )
    (net (code "47") (name "Net-(U4-QA)") (class "Default")
      (node (ref "RR21") (pin "1") (pinfunction "1_1") (pintype "passive"))
      (node (ref "U4") (pin "15") (pinfunction "QA_15") (pintype "passive"))
    )
    (net (code "48") (name "Net-(U4-QB)") (class "Default")
      (node (ref "RR22") (pin "1") (pinfunction "1_1") (pintype "passive"))
      (node (ref "U4") (pin "1") (pinfunction "QB_1") (pintype "passive"))
    )
    (net (code "49") (name "Net-(U4-QC)") (class "Default")
      (node (ref "RR23") (pin "1") (pinfunction "1_1") (pintype "passive"))
      (node (ref "U4") (pin "2") (pinfunction "QC_2") (pintype "passive"))
    )
    (net (code "50") (name "Net-(U4-QD)") (class "Default")
      (node (ref "RR24") (pin "1") (pinfunction "1_1") (pintype "passive"))
      (node (ref "U4") (pin "3") (pinfunction "QD_3") (pintype "passive"))
    )
    (net (code "51") (name "Net-(U4-QE)") (class "Default")
      (node (ref "RR25") (pin "1") (pinfunction "1_1") (pintype "passive"))
      (node (ref "U4") (pin "4") (pinfunction "QE_4") (pintype "passive"))
    )
    (net (code "52") (name "Net-(U4-QF)") (class "Default")
      (node (ref "RR26") (pin "1") (pinfunction "1_1") (pintype "passive"))
      (node (ref "U4") (pin "5") (pinfunction "QF_5") (pintype "passive"))
    )
    (net (code "53") (name "Net-(U4-QG)") (class "Default")
      (node (ref "RR27") (pin "1") (pinfunction "1_1") (pintype "passive"))
      (node (ref "U4") (pin "6") (pinfunction "QG_6") (pintype "passive"))
    )
    (net (code "54") (name "Net-(U4-QH)") (class "Default")
      (node (ref "RR28") (pin "1") (pinfunction "1_1") (pintype "passive"))
      (node (ref "U4") (pin "7") (pinfunction "QH_7") (pintype "passive"))
    )
    (net (code "55") (name "Net-(U5-QA)") (class "Default")
      (node (ref "RR29") (pin "1") (pinfunction "1_1") (pintype "passive"))
      (node (ref "U5") (pin "15") (pinfunction "QA_15") (pintype "passive"))
    )
    (net (code "56") (name "Net-(U5-QB)") (class "Default")
      (node (ref "RR30") (pin "1") (pinfunction "1_1") (pintype "passive"))
      (node (ref "U5") (pin "1") (pinfunction "QB_1") (pintype "passive"))
    )
    (net (code "57") (name "Net-(U5-QC)") (class "Default")
      (node (ref "RR31") (pin "1") (pinfunction "1_1") (pintype "passive"))
      (node (ref "U5") (pin "2") (pinfunction "QC_2") (pintype "passive"))
    )
    (net (code "58") (name "Net-(U5-QD)") (class "Default")
      (node (ref "RR32") (pin "1") (pinfunction "1_1") (pintype "passive"))
      (node (ref "U5") (pin "3") (pinfunction "QD_3") (pintype "passive"))
    )
    (net (code "59") (name "Net-(U5-QE)") (class "Default")
      (node (ref "RR33") (pin "1") (pinfunction "1_1") (pintype "passive"))
      (node (ref "U5") (pin "4") (pinfunction "QE_4") (pintype "passive"))
    )
    (net (code "60") (name "Net-(U5-QF)") (class "Default")
      (node (ref "RR34") (pin "1") (pinfunction "1_1") (pintype "passive"))
      (node (ref "U5") (pin "5") (pinfunction "QF_5") (pintype "passive"))
    )
    (net (code "61") (name "Net-(U5-QG)") (class "Default")
      (node (ref "RR35") (pin "1") (pinfunction "1_1") (pintype "passive"))
      (node (ref "U5") (pin "6") (pinfunction "QG_6") (pintype "passive"))
    )
    (net (code "62") (name "Net-(U5-QH)") (class "Default")
      (node (ref "RR36") (pin "1") (pinfunction "1_1") (pintype "passive"))
      (node (ref "U5") (pin "7") (pinfunction "QH_7") (pintype "passive"))
    )
    (net (code "63") (name "Net-(U6-QA)") (class "Default")
      (node (ref "RR37") (pin "1") (pinfunction "1_1") (pintype "passive"))
      (node (ref "U6") (pin "15") (pinfunction "QA_15") (pintype "passive"))
    )
    (net (code "64") (name "Net-(U6-QB)") (class "Default")
      (node (ref "RR38") (pin "1") (pinfunction "1_1") (pintype "passive"))
      (node (ref "U6") (pin "1") (pinfunction "QB_1") (pintype "passive"))
    )
    (net (code "65") (name "Net-(U6-QC)") (class "Default")
      (node (ref "RR39") (pin "1") (pinfunction "1_1") (pintype "passive"))
      (node (ref "U6") (pin "2") (pinfunction "QC_2") (pintype "passive"))
    )
    (net (code "66") (name "Net-(U6-QD)") (class "Default")
      (node (ref "RR40") (pin "1") (pinfunction "1_1") (pintype "passive"))
      (node (ref "U6") (pin "3") (pinfunction "QD_3") (pintype "passive"))
    )
    (net (code "67") (name "unconnected-(U4-QH#-Pad9)") (class "Default")
      (node (ref "U4") (pin "9") (pinfunction "QH#_9") (pintype "passive"))
    )
    (net (code "68") (name "unconnected-(U5-QH#-Pad9)") (class "Default")
      (node (ref "U5") (pin "9") (pinfunction "QH#_9") (pintype "passive"))
    )
    (net (code "69") (name "unconnected-(U6-QE-Pad4)") (class "Default")
      (node (ref "U6") (pin "4") (pinfunction "QE_4") (pintype "passive"))
    )
    (net (code "70") (name "unconnected-(U6-QF-Pad5)") (class "Default")
      (node (ref "U6") (pin "5") (pinfunction "QF_5") (pintype "passive"))
    )
    (net (code "71") (name "unconnected-(U6-QG-Pad6)") (class "Default")
      (node (ref "U6") (pin "6") (pinfunction "QG_6") (pintype "passive"))
    )
    (net (code "72") (name "unconnected-(U6-QH#-Pad9)") (class "Default")
      (node (ref "U6") (pin "9") (pinfunction "QH#_9") (pintype "passive"))
    )
    (net (code "73") (name "unconnected-(U6-QH-Pad7)") (class "Default")
      (node (ref "U6") (pin "7") (pinfunction "QH_7") (pintype "passive"))
    )
  )
)
